# 15_MOV8.net
KiCad netlist of a schematic drawn in EAGLE
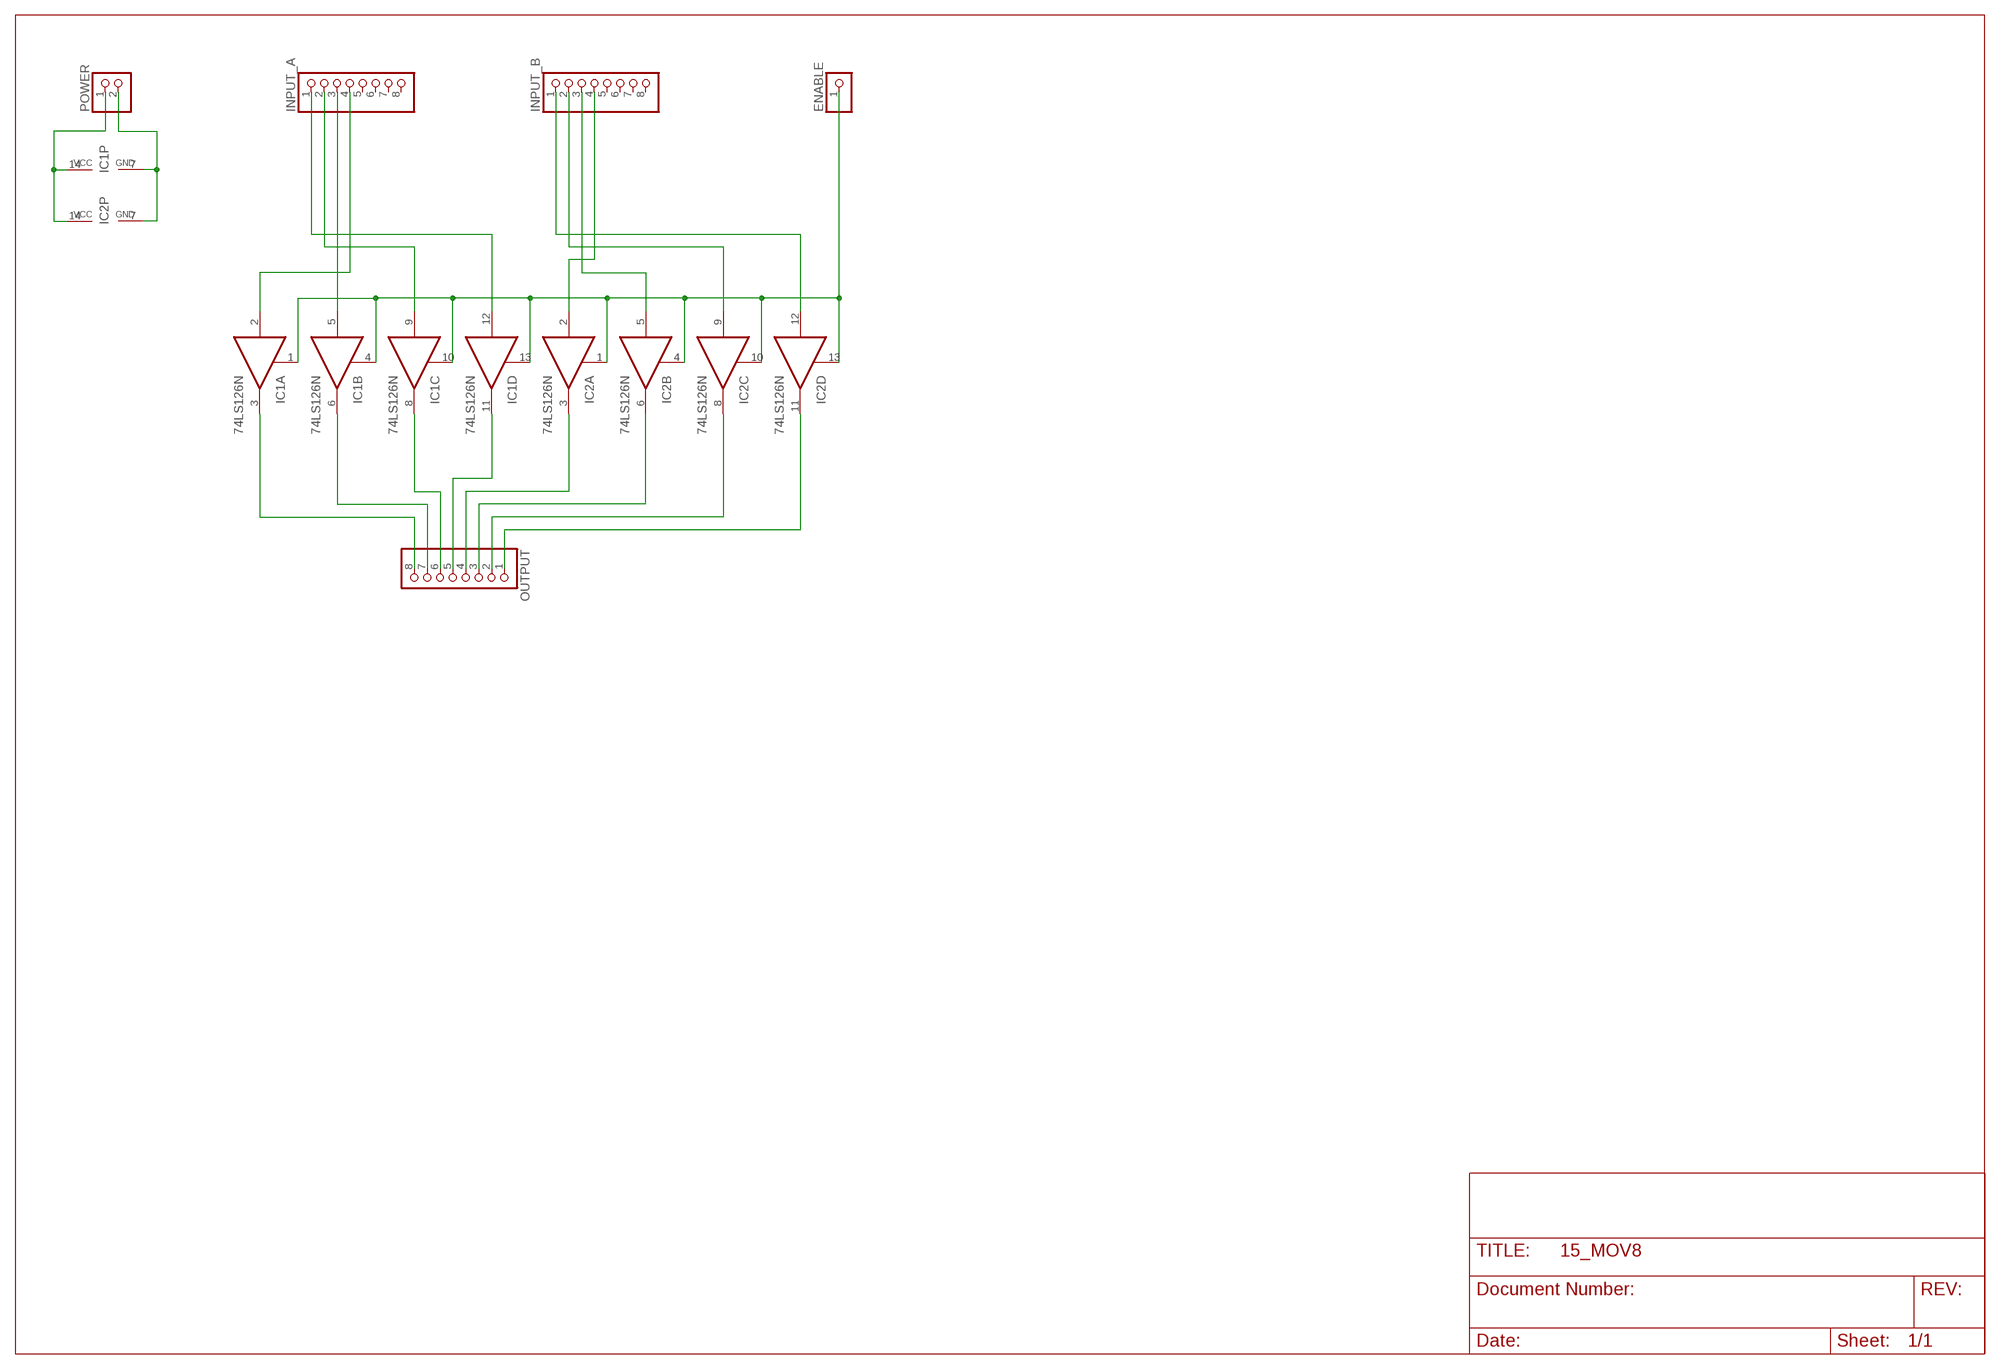
[diagram p0: schematic, sheet 1]

(export (version "E")
  (design (tool "Eeschema 10.0.6"))
  (components
    (comp (ref "ENABLE")
      (value "PINHD-1X1")
      (footprint "eagle-import:1X01")
      (libsource (lib "eagle-import") (part "PINHD-1X1"))
    )
    (comp (ref "IC1")
      (value "74LS126N")
      (footprint "eagle-import:DIL14")
      (libsource (lib "eagle-import") (part "74126NLS"))
    )
    (comp (ref "IC2")
      (value "74LS126N")
      (footprint "eagle-import:DIL14")
      (libsource (lib "eagle-import") (part "74126NLS"))
    )
    (comp (ref "INPUT_A")
      (value "PINHD-1X8")
      (footprint "eagle-import:1X08")
      (libsource (lib "eagle-import") (part "PINHD-1X8"))
    )
    (comp (ref "INPUT_B")
      (value "PINHD-1X8")
      (footprint "eagle-import:1X08")
      (libsource (lib "eagle-import") (part "PINHD-1X8"))
    )
    (comp (ref "OUTPUT")
      (value "PINHD-1X8")
      (footprint "eagle-import:1X08")
      (libsource (lib "eagle-import") (part "PINHD-1X8"))
    )
    (comp (ref "POWER")
      (value "PINHD-1X2")
      (footprint "eagle-import:1X02")
      (libsource (lib "eagle-import") (part "PINHD-1X2"))
    )
  )
  (nets
    (net (code "1") (name "Net-(IC1A-I)") (class "Default")
      (node (ref "IC1") (pin "2") (pinfunction "I_2") (pintype "input"))
      (node (ref "INPUT_A") (pin "4") (pinfunction "4_4") (pintype "passive"))
    )
    (net (code "2") (name "Net-(IC1A-O)") (class "Default")
      (node (ref "IC1") (pin "3") (pinfunction "O_3") (pintype "output"))
      (node (ref "OUTPUT") (pin "8") (pinfunction "8_8") (pintype "passive"))
    )
    (net (code "3") (name "Net-(IC1A-OE)") (class "Default")
      (node (ref "ENABLE") (pin "1") (pinfunction "1_1") (pintype "passive"))
      (node (ref "IC1") (pin "1") (pinfunction "OE_1") (pintype "input"))
      (node (ref "IC1") (pin "10") (pinfunction "OE_10") (pintype "input"))
      (node (ref "IC1") (pin "13") (pinfunction "OE_13") (pintype "input"))
      (node (ref "IC1") (pin "4") (pinfunction "OE_4") (pintype "input"))
      (node (ref "IC2") (pin "1") (pinfunction "OE_1") (pintype "input"))
      (node (ref "IC2") (pin "10") (pinfunction "OE_10") (pintype "input"))
      (node (ref "IC2") (pin "13") (pinfunction "OE_13") (pintype "input"))
      (node (ref "IC2") (pin "4") (pinfunction "OE_4") (pintype "input"))
    )
    (net (code "4") (name "Net-(IC1B-I)") (class "Default")
      (node (ref "IC1") (pin "5") (pinfunction "I_5") (pintype "input"))
      (node (ref "INPUT_A") (pin "3") (pinfunction "3_3") (pintype "passive"))
    )
    (net (code "5") (name "Net-(IC1B-O)") (class "Default")
      (node (ref "IC1") (pin "6") (pinfunction "O_6") (pintype "output"))
      (node (ref "OUTPUT") (pin "7") (pinfunction "7_7") (pintype "passive"))
    )
    (net (code "6") (name "Net-(IC1C-I)") (class "Default")
      (node (ref "IC1") (pin "9") (pinfunction "I_9") (pintype "input"))
      (node (ref "INPUT_A") (pin "2") (pinfunction "2_2") (pintype "passive"))
    )
    (net (code "7") (name "Net-(IC1C-O)") (class "Default")
      (node (ref "IC1") (pin "8") (pinfunction "O_8") (pintype "output"))
      (node (ref "OUTPUT") (pin "6") (pinfunction "6_6") (pintype "passive"))
    )
    (net (code "8") (name "Net-(IC1D-I)") (class "Default")
      (node (ref "IC1") (pin "12") (pinfunction "I_12") (pintype "input"))
      (node (ref "INPUT_A") (pin "1") (pinfunction "1_1") (pintype "passive"))
    )
    (net (code "9") (name "Net-(IC1D-O)") (class "Default")
      (node (ref "IC1") (pin "11") (pinfunction "O_11") (pintype "output"))
      (node (ref "OUTPUT") (pin "5") (pinfunction "5_5") (pintype "passive"))
    )
    (net (code "10") (name "Net-(IC1E-GND)") (class "Default")
      (node (ref "IC1") (pin "7") (pinfunction "GND_7") (pintype "power_in"))
      (node (ref "IC2") (pin "7") (pinfunction "GND_7") (pintype "power_in"))
      (node (ref "POWER") (pin "2") (pinfunction "2_2") (pintype "passive"))
    )
    (net (code "11") (name "Net-(IC1E-VCC)") (class "Default")
      (node (ref "IC1") (pin "14") (pinfunction "VCC_14") (pintype "power_in"))
      (node (ref "IC2") (pin "14") (pinfunction "VCC_14") (pintype "power_in"))
      (node (ref "POWER") (pin "1") (pinfunction "1_1") (pintype "passive"))
    )
    (net (code "12") (name "Net-(IC2A-I)") (class "Default")
      (node (ref "IC2") (pin "2") (pinfunction "I_2") (pintype "input"))
      (node (ref "INPUT_B") (pin "4") (pinfunction "4_4") (pintype "passive"))
    )
    (net (code "13") (name "Net-(IC2A-O)") (class "Default")
      (node (ref "IC2") (pin "3") (pinfunction "O_3") (pintype "output"))
      (node (ref "OUTPUT") (pin "4") (pinfunction "4_4") (pintype "passive"))
    )
    (net (code "14") (name "Net-(IC2B-I)") (class "Default")
      (node (ref "IC2") (pin "5") (pinfunction "I_5") (pintype "input"))
      (node (ref "INPUT_B") (pin "3") (pinfunction "3_3") (pintype "passive"))
    )
    (net (code "15") (name "Net-(IC2B-O)") (class "Default")
      (node (ref "IC2") (pin "6") (pinfunction "O_6") (pintype "output"))
      (node (ref "OUTPUT") (pin "3") (pinfunction "3_3") (pintype "passive"))
    )
    (net (code "16") (name "Net-(IC2C-I)") (class "Default")
      (node (ref "IC2") (pin "9") (pinfunction "I_9") (pintype "input"))
      (node (ref "INPUT_B") (pin "2") (pinfunction "2_2") (pintype "passive"))
    )
    (net (code "17") (name "Net-(IC2C-O)") (class "Default")
      (node (ref "IC2") (pin "8") (pinfunction "O_8") (pintype "output"))
      (node (ref "OUTPUT") (pin "2") (pinfunction "2_2") (pintype "passive"))
    )
    (net (code "18") (name "Net-(IC2D-I)") (class "Default")
      (node (ref "IC2") (pin "12") (pinfunction "I_12") (pintype "input"))
      (node (ref "INPUT_B") (pin "1") (pinfunction "1_1") (pintype "passive"))
    )
    (net (code "19") (name "Net-(IC2D-O)") (class "Default")
      (node (ref "IC2") (pin "11") (pinfunction "O_11") (pintype "output"))
      (node (ref "OUTPUT") (pin "1") (pinfunction "1_1") (pintype "passive"))
    )
    (net (code "20") (name "unconnected-(INPUT_A-Pad5)") (class "Default")
      (node (ref "INPUT_A") (pin "5") (pinfunction "5_5") (pintype "passive"))
    )
    (net (code "21") (name "unconnected-(INPUT_A-Pad6)") (class "Default")
      (node (ref "INPUT_A") (pin "6") (pinfunction "6_6") (pintype "passive"))
    )
    (net (code "22") (name "unconnected-(INPUT_A-Pad7)") (class "Default")
      (node (ref "INPUT_A") (pin "7") (pinfunction "7_7") (pintype "passive"))
    )
    (net (code "23") (name "unconnected-(INPUT_A-Pad8)") (class "Default")
      (node (ref "INPUT_A") (pin "8") (pinfunction "8_8") (pintype "passive"))
    )
    (net (code "24") (name "unconnected-(INPUT_B-Pad5)") (class "Default")
      (node (ref "INPUT_B") (pin "5") (pinfunction "5_5") (pintype "passive"))
    )
    (net (code "25") (name "unconnected-(INPUT_B-Pad6)") (class "Default")
      (node (ref "INPUT_B") (pin "6") (pinfunction "6_6") (pintype "passive"))
    )
    (net (code "26") (name "unconnected-(INPUT_B-Pad7)") (class "Default")
      (node (ref "INPUT_B") (pin "7") (pinfunction "7_7") (pintype "passive"))
    )
    (net (code "27") (name "unconnected-(INPUT_B-Pad8)") (class "Default")
      (node (ref "INPUT_B") (pin "8") (pinfunction "8_8") (pintype "passive"))
    )
  )
)
